# RAT.net
KiCad netlist of a schematic drawn in EAGLE
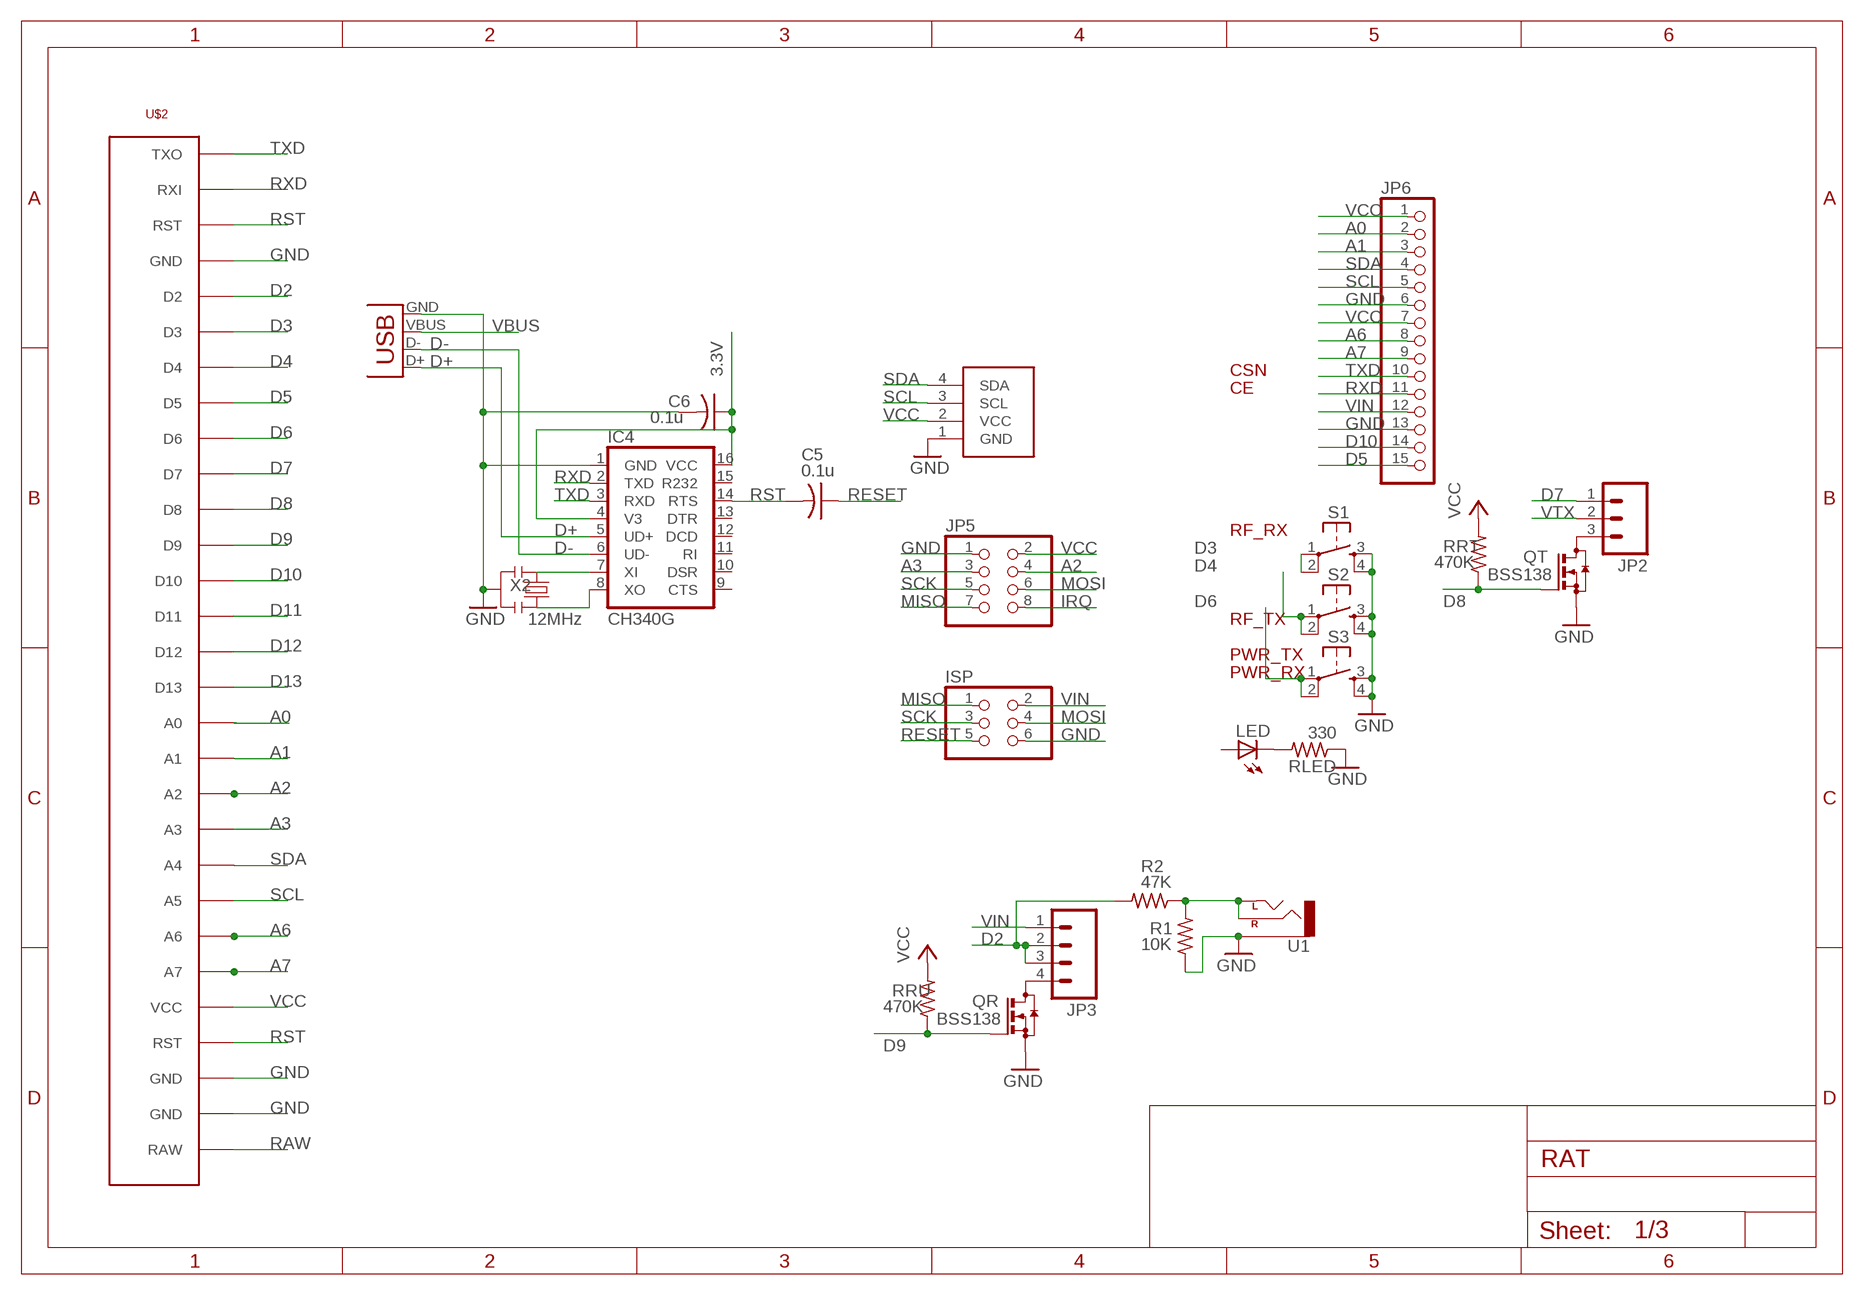
[diagram p0: schematic, sheet 1]
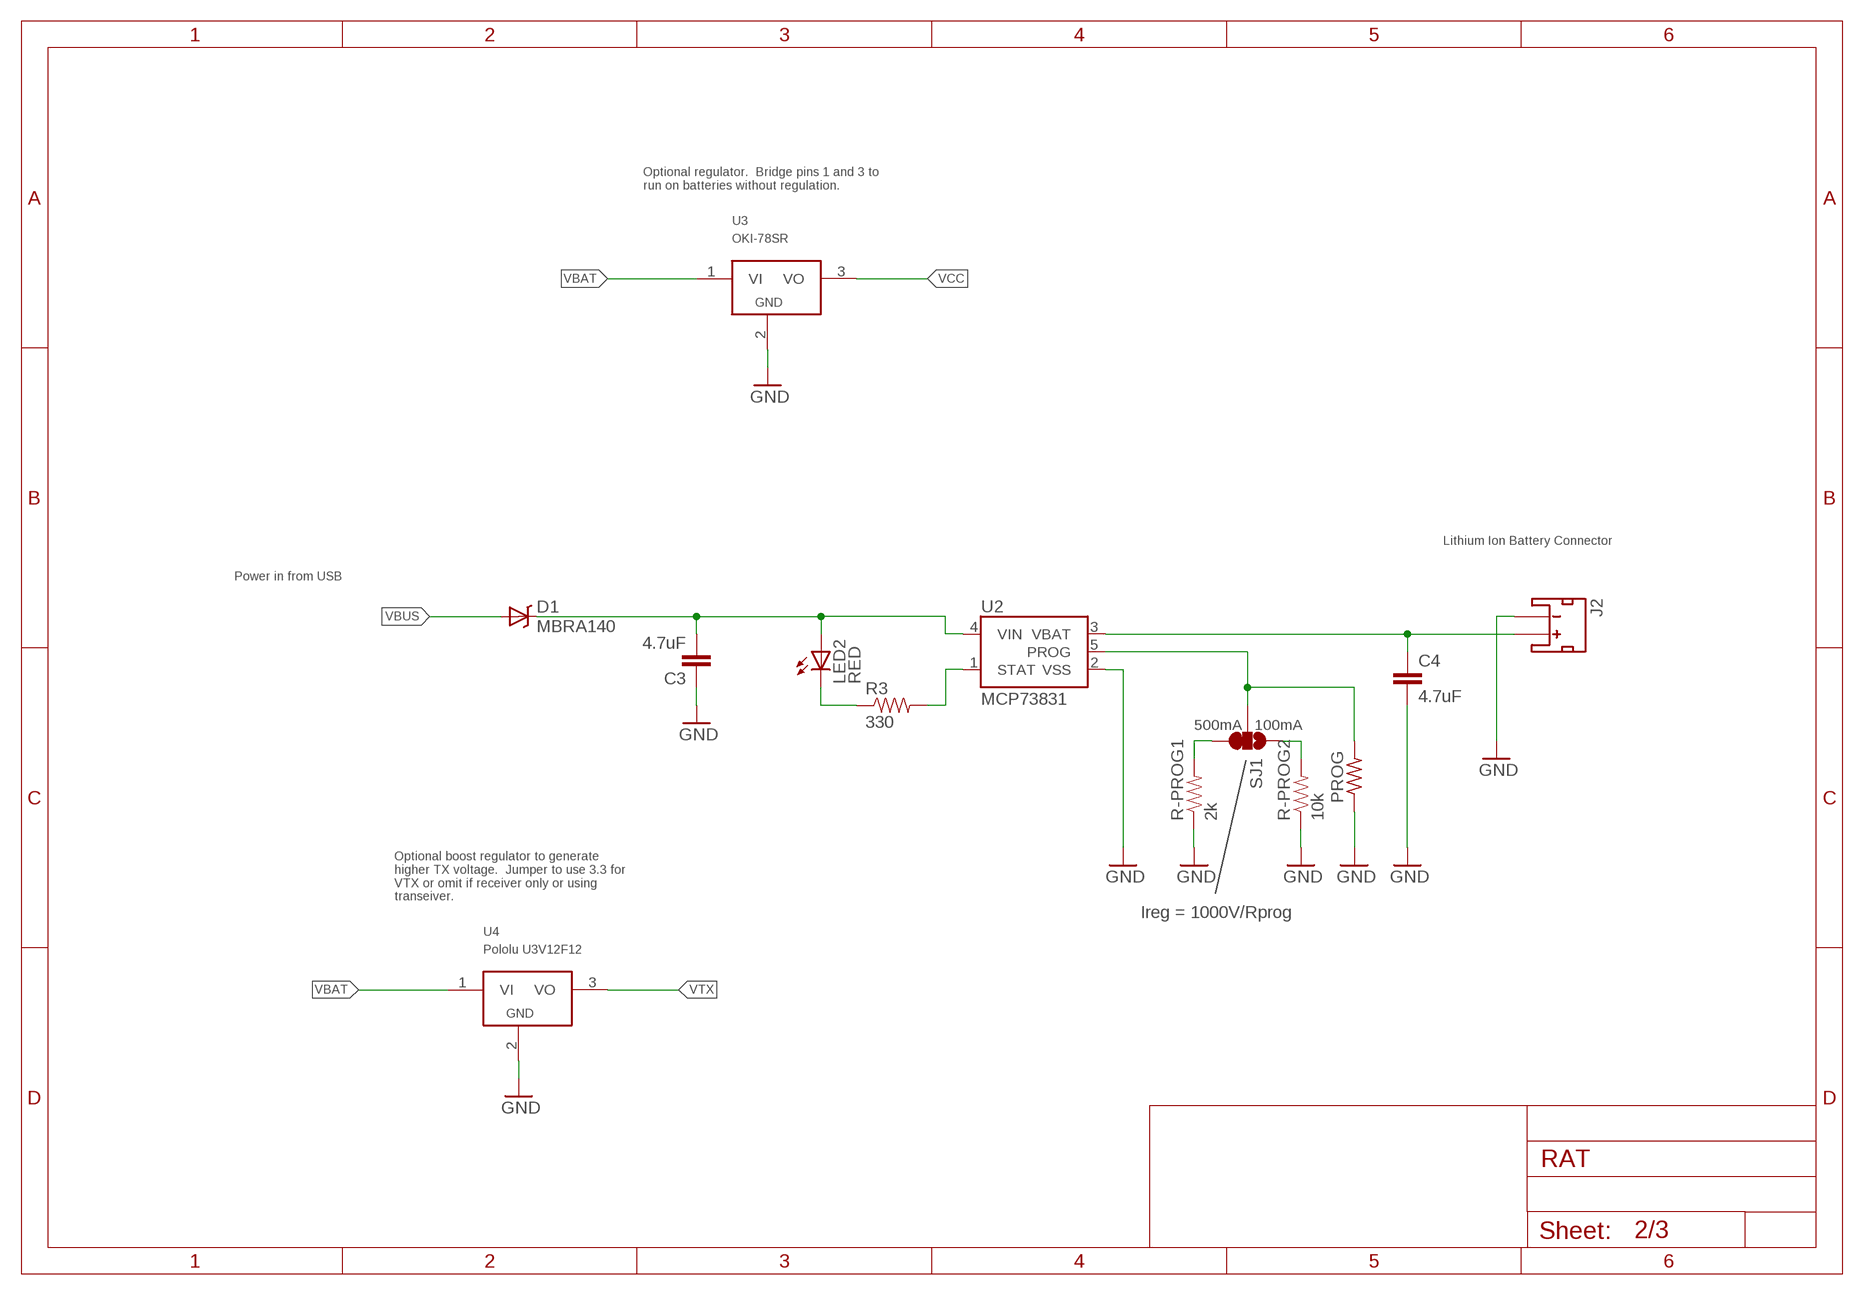
[diagram p1: schematic, sheet 2]

(export (version "E")
  (design (tool "Eeschema 10.0.6"))
  (components
    (comp (ref "C5")
      (value "0.1u")
      (footprint "eagle-import:C0805K")
      (libsource (lib "eagle-import") (part "C-USC0805K"))
    )
    (comp (ref "C6")
      (value "0.1u")
      (footprint "eagle-import:C0805K")
      (libsource (lib "eagle-import") (part "C-USC0805K"))
    )
    (comp (ref "IC4")
      (value "CH340G")
      (footprint "eagle-import:SO16")
      (libsource (lib "eagle-import") (part "CH340G"))
    )
    (comp (ref "ISP")
      (value "PINHD-2X3")
      (footprint "eagle-import:2X03")
      (libsource (lib "eagle-import") (part "PINHD-2X3"))
    )
    (comp (ref "JP2")
      (value "M03LOCK_LONGPADS")
      (footprint "eagle-import:1X03_LOCK_LONGPADS")
      (libsource (lib "eagle-import") (part "M03LOCK_LONGPADS"))
    )
    (comp (ref "JP3")
      (value "M04LOCK")
      (footprint "eagle-import:1X04_LOCK")
      (libsource (lib "eagle-import") (part "M04LOCK"))
    )
    (comp (ref "JP5")
      (value "PINHD-2X4")
      (footprint "eagle-import:2X04")
      (libsource (lib "eagle-import") (part "PINHD-2X4"))
    )
    (comp (ref "JP6")
      (value "PINHD-1X15-CB")
      (footprint "eagle-import:1X15-CB")
      (libsource (lib "eagle-import") (part "PINHD-1X15-CB"))
    )
    (comp (ref "LED")
      (value "LEDCHIPLED_0805")
      (footprint "eagle-import:CHIPLED_0805")
      (libsource (lib "eagle-import") (part "LEDCHIPLED_0805"))
    )
    (comp (ref "QR")
      (value "BSS138")
      (footprint "eagle-import:SOT23")
      (libsource (lib "eagle-import") (part "BSS123"))
    )
    (comp (ref "QT")
      (value "BSS138")
      (footprint "eagle-import:SOT23")
      (libsource (lib "eagle-import") (part "BSS123"))
    )
    (comp (ref "R1")
      (value "10K")
      (footprint "eagle-import:R0805")
      (libsource (lib "eagle-import") (part "R-US_R0805"))
    )
    (comp (ref "R2")
      (value "47K")
      (footprint "eagle-import:R0805")
      (libsource (lib "eagle-import") (part "R-US_R0805"))
    )
    (comp (ref "RLED")
      (value "330")
      (footprint "eagle-import:R0805")
      (libsource (lib "eagle-import") (part "R-US_R0805"))
    )
    (comp (ref "RRT")
      (value "470K")
      (footprint "eagle-import:R0805")
      (libsource (lib "eagle-import") (part "R-US_R0805"))
    )
    (comp (ref "RRU")
      (value "470K")
      (footprint "eagle-import:R0805")
      (libsource (lib "eagle-import") (part "R-US_R0805"))
    )
    (comp (ref "S1")
      (value "TAC_SWITCHPTH")
      (footprint "eagle-import:TACTILE-PTH")
      (libsource (lib "eagle-import") (part "TAC_SWITCHPTH"))
    )
    (comp (ref "S2")
      (value "TAC_SWITCHPTH")
      (footprint "eagle-import:TACTILE-PTH")
      (libsource (lib "eagle-import") (part "TAC_SWITCHPTH"))
    )
    (comp (ref "S3")
      (value "TAC_SWITCHPTH")
      (footprint "eagle-import:TACTILE-PTH")
      (libsource (lib "eagle-import") (part "TAC_SWITCHPTH"))
    )
    (comp (ref "U$1")
      (value "SSD1306_OLED_I2C")
      (footprint "eagle-import:SSD1306_OLED_I2C")
      (libsource (lib "eagle-import") (part "SSD1306_OLED_I2C"))
    )
    (comp (ref "U$2")
      (value "ARDUINO-PRO-MINI-CORRECT")
      (footprint "eagle-import:ARDUINO-PRO-MINI")
      (libsource (lib "eagle-import") (part "ARDUINO-PRO-MINI-CORRECT"))
    )
    (comp (ref "U1")
      (value "AUDIO-JACKPTH")
      (footprint "eagle-import:AUDIO-JACK")
      (libsource (lib "eagle-import") (part "AUDIO-JACKPTH"))
    )
    (comp (ref "X1")
      (value "USBSMD")
      (footprint "eagle-import:USB-MINIB")
      (libsource (lib "eagle-import") (part "USBSMD"))
    )
    (comp (ref "X2")
      (value "12MHz")
      (footprint "eagle-import:RESONATOR-SMD")
      (libsource (lib "eagle-import") (part "RESONATORSMD"))
    )
    (comp (ref "C3")
      (value "4.7uF")
      (footprint "eagle-import:0603-CAP")
      (libsource (lib "eagle-import") (part "4.7UF-6.3V-10%(0603)0603"))
    )
    (comp (ref "C4")
      (value "4.7uF")
      (footprint "eagle-import:0603-CAP")
      (libsource (lib "eagle-import") (part "4.7UF-6.3V-10%(0603)0603"))
    )
    (comp (ref "D1")
      (value "MBRA140")
      (footprint "eagle-import:SMA-DIODE")
      (libsource (lib "eagle-import") (part "MBRA140"))
    )
    (comp (ref "J2")
      (value "JST_2MM_MALE")
      (footprint "eagle-import:JST-2-SMD")
      (libsource (lib "eagle-import") (part "JST_2MM_MALE"))
    )
    (comp (ref "LED2")
      (value "RED")
      (footprint "eagle-import:LED-0603")
      (libsource (lib "eagle-import") (part "LED-RED0603"))
    )
    (comp (ref "PROG")
      (value "R-US_R0603")
      (footprint "eagle-import:R0603")
      (libsource (lib "eagle-import") (part "rcl_R-US_R0603"))
    )
    (comp (ref "R-PROG1")
      (value "2k")
      (footprint "eagle-import:0603-RES")
      (libsource (lib "eagle-import") (part "2.0KOHM1/10W5%(0603)"))
    )
    (comp (ref "R-PROG2")
      (value "10k")
      (footprint "eagle-import:0603-RES")
      (libsource (lib "eagle-import") (part "10KOHM1/10W1%(0603)0603"))
    )
    (comp (ref "R3")
      (value "330")
      (footprint "eagle-import:0603-RES")
      (libsource (lib "eagle-import") (part "330OHM1/10W1%(0603)"))
    )
    (comp (ref "SJ1")
      (value "SOLDERJUMPER_2WAYS")
      (footprint "eagle-import:SJ_3")
      (libsource (lib "eagle-import") (part "SOLDERJUMPER_2WAYS"))
    )
    (comp (ref "U2")
      (value "MCP73831")
      (footprint "eagle-import:SOT23-5")
      (libsource (lib "eagle-import") (part "MCP73831"))
    )
    (comp (ref "U3")
      (value "OKI-78SR")
      (footprint "eagle-import:TO-220")
      (libsource (lib "eagle-import") (part "OKI-78SR"))
    )
    (comp (ref "U4")
      (value "Pololu U3V12F12")
      (footprint "eagle-import:TO-220")
      (libsource (lib "eagle-import") (part "OKI-78SR"))
    )
  )
  (nets
    (net (code "1") (name "3.3V") (class "Default")
      (node (ref "C6") (pin "1") (pinfunction "1_1") (pintype "passive"))
      (node (ref "IC4") (pin "16") (pinfunction "VCC_16") (pintype "power_in"))
      (node (ref "IC4") (pin "4") (pinfunction "V3_4") (pintype "bidirectional"))
    )
    (net (code "2") (name "A0") (class "Default")
      (node (ref "JP6") (pin "2") (pinfunction "2_2") (pintype "passive"))
      (node (ref "U$2") (pin "A0") (pinfunction "A0_A0") (pintype "bidirectional"))
    )
    (net (code "3") (name "A1") (class "Default")
      (node (ref "JP6") (pin "3") (pinfunction "3_3") (pintype "passive"))
      (node (ref "U$2") (pin "A1") (pinfunction "A1_A1") (pintype "bidirectional"))
    )
    (net (code "4") (name "A2") (class "Default")
      (node (ref "JP5") (pin "4") (pinfunction "4_4") (pintype "passive"))
      (node (ref "U$2") (pin "A2") (pinfunction "A2_A2") (pintype "bidirectional"))
    )
    (net (code "5") (name "A3") (class "Default")
      (node (ref "JP5") (pin "3") (pinfunction "3_3") (pintype "passive"))
      (node (ref "U$2") (pin "A3") (pinfunction "A3_A3") (pintype "bidirectional"))
    )
    (net (code "6") (name "A6") (class "Default")
      (node (ref "JP6") (pin "8") (pinfunction "8_8") (pintype "passive"))
      (node (ref "U$2") (pin "A6@1") (pinfunction "A6_A6@1") (pintype "bidirectional"))
      (node (ref "U$2") (pin "A6@2") (pinfunction "A6_A6@2") (pintype "bidirectional"))
    )
    (net (code "7") (name "A7") (class "Default")
      (node (ref "JP6") (pin "9") (pinfunction "9_9") (pintype "passive"))
      (node (ref "U$2") (pin "A7@1") (pinfunction "A7_A7@1") (pintype "bidirectional"))
      (node (ref "U$2") (pin "A7@2") (pinfunction "A7_A7@2") (pintype "bidirectional"))
    )
    (net (code "8") (name "D+") (class "Default")
      (node (ref "IC4") (pin "5") (pinfunction "UD+_5") (pintype "bidirectional"))
      (node (ref "X1") (pin "D+") (pinfunction "D+_D+") (pintype "bidirectional"))
    )
    (net (code "9") (name "D-") (class "Default")
      (node (ref "IC4") (pin "6") (pinfunction "UD-_6") (pintype "bidirectional"))
      (node (ref "X1") (pin "D-") (pinfunction "D-_D-") (pintype "bidirectional"))
    )
    (net (code "10") (name "D2") (class "Default")
      (node (ref "JP3") (pin "2") (pinfunction "2_2") (pintype "passive"))
      (node (ref "JP3") (pin "3") (pinfunction "3_3") (pintype "passive"))
      (node (ref "R2") (pin "2") (pinfunction "2_2") (pintype "passive"))
      (node (ref "U$2") (pin "2") (pinfunction "D2_2") (pintype "bidirectional"))
    )
    (net (code "11") (name "D3") (class "Default")
      (node (ref "S1") (pin "1") (pinfunction "1_1") (pintype "passive"))
      (node (ref "S1") (pin "2") (pinfunction "2_2") (pintype "passive"))
      (node (ref "U$2") (pin "3") (pinfunction "D3_3") (pintype "bidirectional"))
    )
    (net (code "12") (name "D4") (class "Default")
      (node (ref "S2") (pin "1") (pinfunction "1_1") (pintype "passive"))
      (node (ref "S2") (pin "2") (pinfunction "2_2") (pintype "passive"))
      (node (ref "U$2") (pin "4") (pinfunction "D4_4") (pintype "bidirectional"))
    )
    (net (code "13") (name "D5") (class "Default")
      (node (ref "JP6") (pin "15") (pinfunction "15_15") (pintype "passive"))
      (node (ref "U$2") (pin "5") (pinfunction "D5_5") (pintype "bidirectional"))
    )
    (net (code "14") (name "D6") (class "Default")
      (node (ref "S3") (pin "1") (pinfunction "1_1") (pintype "passive"))
      (node (ref "S3") (pin "2") (pinfunction "2_2") (pintype "passive"))
      (node (ref "U$2") (pin "6") (pinfunction "D6_6") (pintype "bidirectional"))
    )
    (net (code "15") (name "D7") (class "Default")
      (node (ref "JP2") (pin "1") (pinfunction "1_1") (pintype "passive"))
      (node (ref "U$2") (pin "7") (pinfunction "D7_7") (pintype "bidirectional"))
    )
    (net (code "16") (name "D8") (class "Default")
      (node (ref "QT") (pin "1") (pinfunction "G_1") (pintype "passive"))
      (node (ref "RRT") (pin "1") (pinfunction "1_1") (pintype "passive"))
      (node (ref "U$2") (pin "8") (pinfunction "D8_8") (pintype "bidirectional"))
    )
    (net (code "17") (name "D9") (class "Default")
      (node (ref "QR") (pin "1") (pinfunction "G_1") (pintype "passive"))
      (node (ref "RRU") (pin "1") (pinfunction "1_1") (pintype "passive"))
      (node (ref "U$2") (pin "9") (pinfunction "D9_9") (pintype "bidirectional"))
    )
    (net (code "18") (name "D10") (class "Default")
      (node (ref "JP6") (pin "14") (pinfunction "14_14") (pintype "passive"))
      (node (ref "U$2") (pin "10") (pinfunction "D10_10") (pintype "bidirectional"))
    )
    (net (code "19") (name "D11") (class "Default")
      (node (ref "U$2") (pin "11") (pinfunction "D11_11") (pintype "bidirectional"))
    )
    (net (code "20") (name "D12") (class "Default")
      (node (ref "U$2") (pin "12") (pinfunction "D12_12") (pintype "bidirectional"))
    )
    (net (code "21") (name "D13") (class "Default")
      (node (ref "U$2") (pin "13") (pinfunction "D13_13") (pintype "bidirectional"))
    )
    (net (code "22") (name "GND") (class "Default")
      (node (ref "C3") (pin "1") (pinfunction "1_1") (pintype "passive"))
      (node (ref "C4") (pin "2") (pinfunction "2_2") (pintype "passive"))
      (node (ref "C6") (pin "2") (pinfunction "2_2") (pintype "passive"))
      (node (ref "IC4") (pin "1") (pinfunction "GND_1") (pintype "power_in"))
      (node (ref "ISP") (pin "6") (pinfunction "6_6") (pintype "passive"))
      (node (ref "J2") (pin "1") (pinfunction "-_1") (pintype "bidirectional"))
      (node (ref "JP5") (pin "1") (pinfunction "1_1") (pintype "passive"))
      (node (ref "JP6") (pin "13") (pinfunction "13_13") (pintype "passive"))
      (node (ref "JP6") (pin "6") (pinfunction "6_6") (pintype "passive"))
      (node (ref "PROG") (pin "1") (pinfunction "1_1") (pintype "passive"))
      (node (ref "QR") (pin "2") (pinfunction "S_2") (pintype "passive"))
      (node (ref "QT") (pin "2") (pinfunction "S_2") (pintype "passive"))
      (node (ref "R-PROG1") (pin "1") (pinfunction "1_1") (pintype "passive"))
      (node (ref "R-PROG2") (pin "1") (pinfunction "1_1") (pintype "passive"))
      (node (ref "R1") (pin "1") (pinfunction "1_1") (pintype "passive"))
      (node (ref "RLED") (pin "1") (pinfunction "1_1") (pintype "passive"))
      (node (ref "S1") (pin "3") (pinfunction "3_3") (pintype "passive"))
      (node (ref "S1") (pin "4") (pinfunction "4_4") (pintype "passive"))
      (node (ref "S2") (pin "3") (pinfunction "3_3") (pintype "passive"))
      (node (ref "S2") (pin "4") (pinfunction "4_4") (pintype "passive"))
      (node (ref "S3") (pin "3") (pinfunction "3_3") (pintype "passive"))
      (node (ref "S3") (pin "4") (pinfunction "4_4") (pintype "passive"))
      (node (ref "U$1") (pin "1") (pinfunction "GND_1") (pintype "power_in"))
      (node (ref "U$2") (pin "GND@1") (pinfunction "GND_GND@1") (pintype "power_in"))
      (node (ref "U$2") (pin "GND@2") (pinfunction "GND_GND@2") (pintype "power_in"))
      (node (ref "U$2") (pin "GND@3") (pinfunction "GND_GND@3") (pintype "power_in"))
      (node (ref "U1") (pin "SLEEVE") (pinfunction "SLEEVE_SLEEVE") (pintype "bidirectional"))
      (node (ref "U2") (pin "2") (pinfunction "VSS_2") (pintype "power_in"))
      (node (ref "U3") (pin "2") (pinfunction "GND_2") (pintype "power_in"))
      (node (ref "U4") (pin "2") (pinfunction "GND_2") (pintype "power_in"))
      (node (ref "X1") (pin "GND") (pinfunction "GND_GND") (pintype "bidirectional"))
      (node (ref "X2") (pin "2") (pinfunction "2_2") (pintype "passive"))
    )
    (net (code "23") (name "IRQ") (class "Default")
      (node (ref "JP5") (pin "8") (pinfunction "8_8") (pintype "passive"))
    )
    (net (code "24") (name "MISO") (class "Default")
      (node (ref "ISP") (pin "1") (pinfunction "1_1") (pintype "passive"))
      (node (ref "JP5") (pin "7") (pinfunction "7_7") (pintype "passive"))
    )
    (net (code "25") (name "MOSI") (class "Default")
      (node (ref "ISP") (pin "4") (pinfunction "4_4") (pintype "passive"))
      (node (ref "JP5") (pin "6") (pinfunction "6_6") (pintype "passive"))
    )
    (net (code "26") (name "Net-(IC4-XI)") (class "Default")
      (node (ref "IC4") (pin "7") (pinfunction "XI_7") (pintype "bidirectional"))
      (node (ref "X2") (pin "1") (pinfunction "1_1") (pintype "passive"))
    )
    (net (code "27") (name "Net-(IC4-XO)") (class "Default")
      (node (ref "IC4") (pin "8") (pinfunction "XO_8") (pintype "bidirectional"))
      (node (ref "X2") (pin "3") (pinfunction "3_3") (pintype "passive"))
    )
    (net (code "28") (name "Net-(LED-PadC)") (class "Default")
      (node (ref "LED") (pin "C") (pinfunction "C_C") (pintype "passive"))
      (node (ref "RLED") (pin "2") (pinfunction "2_2") (pintype "passive"))
    )
    (net (code "29") (name "Net-(LED2-PadC)") (class "Default")
      (node (ref "LED2") (pin "C") (pinfunction "C_C") (pintype "passive"))
      (node (ref "R3") (pin "1") (pinfunction "1_1") (pintype "passive"))
    )
    (net (code "30") (name "Net-(QR-D)") (class "Default")
      (node (ref "JP3") (pin "4") (pinfunction "4_4") (pintype "passive"))
      (node (ref "QR") (pin "3") (pinfunction "D_3") (pintype "passive"))
    )
    (net (code "31") (name "Net-(QT-D)") (class "Default")
      (node (ref "JP2") (pin "3") (pinfunction "3_3") (pintype "passive"))
      (node (ref "QT") (pin "3") (pinfunction "D_3") (pintype "passive"))
    )
    (net (code "32") (name "Net-(R-PROG1-Pad2)") (class "Default")
      (node (ref "R-PROG1") (pin "2") (pinfunction "2_2") (pintype "passive"))
      (node (ref "SJ1") (pin "3") (pinfunction "3_3") (pintype "passive"))
    )
    (net (code "33") (name "Net-(R-PROG2-Pad2)") (class "Default")
      (node (ref "R-PROG2") (pin "2") (pinfunction "2_2") (pintype "passive"))
      (node (ref "SJ1") (pin "1") (pinfunction "1_1") (pintype "passive"))
    )
    (net (code "34") (name "Net-(U1-LEFT)") (class "Default")
      (node (ref "R1") (pin "2") (pinfunction "2_2") (pintype "passive"))
      (node (ref "R2") (pin "1") (pinfunction "1_1") (pintype "passive"))
      (node (ref "U1") (pin "RING") (pinfunction "RIGHT_RING") (pintype "bidirectional"))
      (node (ref "U1") (pin "TIP") (pinfunction "LEFT_TIP") (pintype "bidirectional"))
    )
    (net (code "35") (name "Net-(U2-PROG)") (class "Default")
      (node (ref "PROG") (pin "2") (pinfunction "2_2") (pintype "passive"))
      (node (ref "SJ1") (pin "2") (pinfunction "2_2") (pintype "passive"))
      (node (ref "U2") (pin "5") (pinfunction "PROG_5") (pintype "input"))
    )
    (net (code "36") (name "Net-(U2-STAT)") (class "Default")
      (node (ref "R3") (pin "2") (pinfunction "2_2") (pintype "passive"))
      (node (ref "U2") (pin "1") (pinfunction "STAT_1") (pintype "output"))
    )
    (net (code "37") (name "Net-(U2-VIN)") (class "Default")
      (node (ref "C3") (pin "2") (pinfunction "2_2") (pintype "passive"))
      (node (ref "D1") (pin "C") (pinfunction "C_C") (pintype "passive"))
      (node (ref "LED2") (pin "A") (pinfunction "A_A") (pintype "passive"))
      (node (ref "U2") (pin "4") (pinfunction "VIN_4") (pintype "power_in"))
    )
    (net (code "38") (name "RAW") (class "Default")
      (node (ref "U$2") (pin "RAW") (pinfunction "RAW_RAW") (pintype "power_in"))
    )
    (net (code "39") (name "RESET") (class "Default")
      (node (ref "C5") (pin "1") (pinfunction "1_1") (pintype "passive"))
      (node (ref "ISP") (pin "5") (pinfunction "5_5") (pintype "passive"))
    )
    (net (code "40") (name "RST") (class "Default")
      (node (ref "C5") (pin "2") (pinfunction "2_2") (pintype "passive"))
      (node (ref "IC4") (pin "14") (pinfunction "RTS_14") (pintype "bidirectional"))
      (node (ref "U$2") (pin "RST@1") (pinfunction "RST_RST@1") (pintype "bidirectional"))
      (node (ref "U$2") (pin "RST@2") (pinfunction "RST_RST@2") (pintype "output"))
    )
    (net (code "41") (name "RXD") (class "Default")
      (node (ref "IC4") (pin "2") (pinfunction "TXD_2") (pintype "bidirectional"))
      (node (ref "JP6") (pin "11") (pinfunction "11_11") (pintype "passive"))
      (node (ref "U$2") (pin "RXI") (pinfunction "RXI_RXI") (pintype "bidirectional"))
    )
    (net (code "42") (name "SCK") (class "Default")
      (node (ref "ISP") (pin "3") (pinfunction "3_3") (pintype "passive"))
      (node (ref "JP5") (pin "5") (pinfunction "5_5") (pintype "passive"))
    )
    (net (code "43") (name "SCL") (class "Default")
      (node (ref "JP6") (pin "5") (pinfunction "5_5") (pintype "passive"))
      (node (ref "U$1") (pin "3") (pinfunction "SCL_3") (pintype "bidirectional"))
      (node (ref "U$2") (pin "A5") (pinfunction "A5_A5") (pintype "bidirectional"))
    )
    (net (code "44") (name "SDA") (class "Default")
      (node (ref "JP6") (pin "4") (pinfunction "4_4") (pintype "passive"))
      (node (ref "U$1") (pin "4") (pinfunction "SDA_4") (pintype "bidirectional"))
      (node (ref "U$2") (pin "A4") (pinfunction "A4_A4") (pintype "bidirectional"))
    )
    (net (code "45") (name "TXD") (class "Default")
      (node (ref "IC4") (pin "3") (pinfunction "RXD_3") (pintype "bidirectional"))
      (node (ref "JP6") (pin "10") (pinfunction "10_10") (pintype "passive"))
      (node (ref "U$2") (pin "TXO") (pinfunction "TXO_TXO") (pintype "bidirectional"))
    )
    (net (code "46") (name "VBAT") (class "Default")
      (node (ref "C4") (pin "1") (pinfunction "1_1") (pintype "passive"))
      (node (ref "J2") (pin "2") (pinfunction "+_2") (pintype "bidirectional"))
      (node (ref "U2") (pin "3") (pinfunction "VBAT_3") (pintype "power_in"))
      (node (ref "U3") (pin "1") (pinfunction "VI_1") (pintype "bidirectional"))
      (node (ref "U4") (pin "1") (pinfunction "VI_1") (pintype "bidirectional"))
    )
    (net (code "47") (name "VBUS") (class "Default")
      (node (ref "D1") (pin "A") (pinfunction "A_A") (pintype "passive"))
      (node (ref "X1") (pin "VBUS") (pinfunction "VBUS_VBUS") (pintype "bidirectional"))
    )
    (net (code "48") (name "VCC") (class "Default")
      (node (ref "JP5") (pin "2") (pinfunction "2_2") (pintype "passive"))
      (node (ref "JP6") (pin "1") (pinfunction "1_1") (pintype "passive"))
      (node (ref "JP6") (pin "7") (pinfunction "7_7") (pintype "passive"))
      (node (ref "RRT") (pin "2") (pinfunction "2_2") (pintype "passive"))
      (node (ref "RRU") (pin "2") (pinfunction "2_2") (pintype "passive"))
      (node (ref "U$1") (pin "2") (pinfunction "VCC_2") (pintype "power_in"))
      (node (ref "U$2") (pin "VCC") (pinfunction "VCC_VCC") (pintype "power_in"))
      (node (ref "U3") (pin "3") (pinfunction "VO_3") (pintype "bidirectional"))
    )
    (net (code "49") (name "VIN") (class "Default")
      (node (ref "ISP") (pin "2") (pinfunction "2_2") (pintype "passive"))
      (node (ref "JP3") (pin "1") (pinfunction "1_1") (pintype "passive"))
      (node (ref "JP6") (pin "12") (pinfunction "12_12") (pintype "passive"))
    )
    (net (code "50") (name "VTX") (class "Default")
      (node (ref "JP2") (pin "2") (pinfunction "2_2") (pintype "passive"))
      (node (ref "U4") (pin "3") (pinfunction "VO_3") (pintype "bidirectional"))
    )
    (net (code "51") (name "unconnected-(IC4-CTS-Pad9)") (class "Default")
      (node (ref "IC4") (pin "9") (pinfunction "CTS_9") (pintype "bidirectional"))
    )
    (net (code "52") (name "unconnected-(IC4-DCD-Pad12)") (class "Default")
      (node (ref "IC4") (pin "12") (pinfunction "DCD_12") (pintype "bidirectional"))
    )
    (net (code "53") (name "unconnected-(IC4-DSR-Pad10)") (class "Default")
      (node (ref "IC4") (pin "10") (pinfunction "DSR_10") (pintype "bidirectional"))
    )
    (net (code "54") (name "unconnected-(IC4-DTR-Pad13)") (class "Default")
      (node (ref "IC4") (pin "13") (pinfunction "DTR_13") (pintype "bidirectional"))
    )
    (net (code "55") (name "unconnected-(IC4-R232-Pad15)") (class "Default")
      (node (ref "IC4") (pin "15") (pinfunction "R232_15") (pintype "bidirectional"))
    )
    (net (code "56") (name "unconnected-(IC4-RI-Pad11)") (class "Default")
      (node (ref "IC4") (pin "11") (pinfunction "RI_11") (pintype "bidirectional"))
    )
    (net (code "57") (name "unconnected-(J2-PAD1-PadNC1)") (class "Default")
      (node (ref "J2") (pin "NC1") (pinfunction "PAD1_NC1") (pintype "bidirectional"))
    )
    (net (code "58") (name "unconnected-(J2-PAD2-PadNC2)") (class "Default")
      (node (ref "J2") (pin "NC2") (pinfunction "PAD2_NC2") (pintype "bidirectional"))
    )
    (net (code "59") (name "unconnected-(LED-PadA)") (class "Default")
      (node (ref "LED") (pin "A") (pinfunction "A_A") (pintype "passive"))
    )
  )
)
